# interstage_B2v2.net
KiCad netlist of a schematic drawn in EAGLE
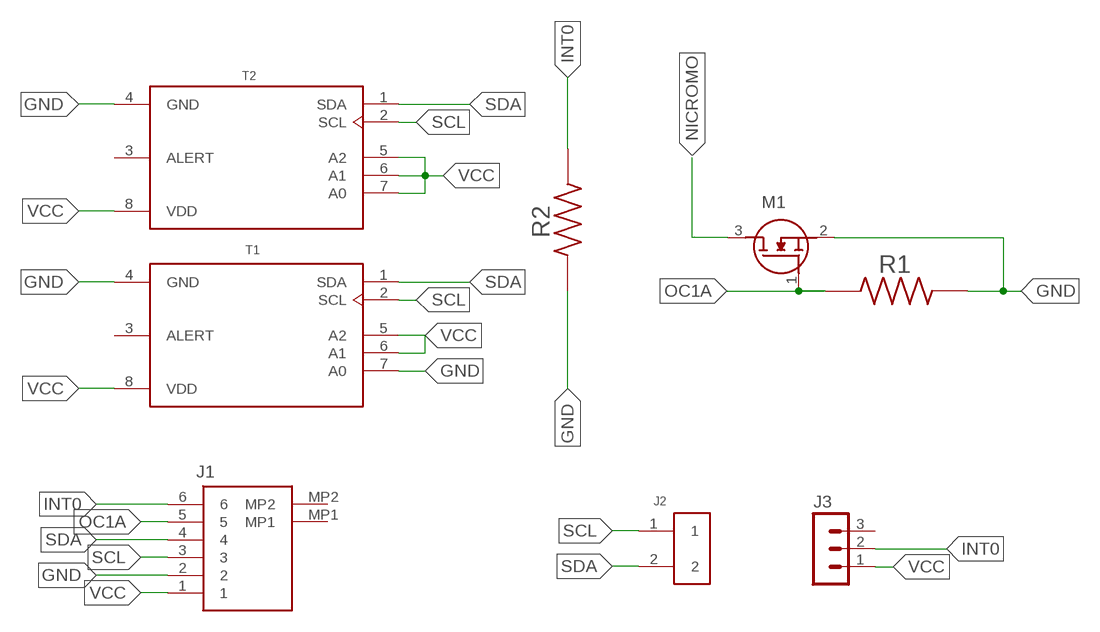
[diagram p0: schematic, sheet 1]

(export (version "E")
  (design (tool "Eeschema 10.0.6"))
  (components
    (comp (ref "J1")
      (value "53261-7006")
      (footprint "eagle-import:532617006")
      (fields (field (name "MOUSER_PART_NUMBER") "538-53261-7006"))
      (libsource (lib "eagle-import") (part "53261-7006"))
    )
    (comp (ref "J2")
      (value "0532610271")
      (footprint "eagle-import:MOLEX_0532610271")
      (fields (field (name "MF") "Molex"))
      (libsource (lib "eagle-import") (part "0532610271"))
    )
    (comp (ref "J3")
      (value "MA03-1")
      (footprint "eagle-import:MA03-1")
      (libsource (lib "eagle-import") (part "MA03-1"))
    )
    (comp (ref "M1")
      (value "PMV16XNR")
      (footprint "eagle-import:SOT95P230X110-3N")
      (fields (field (name "MOUSER_PART_NUMBER") "771-PMV16XNR"))
      (libsource (lib "eagle-import") (part "PMV16XNR"))
    )
    (comp (ref "R1")
      (value "330")
      (footprint "eagle-import:RESC3216X70N")
      (fields
        (field (name "DIGI-KEY_PART_NUMBER") "P330BCCT-ND")
        (field (name "MF") "Panasonic Electronic")
        (field (name "MP") "ERA-8AEB331V")
      )
      (libsource (lib "eagle-import") (part "ERA-8AEB331V"))
    )
    (comp (ref "R2")
      (value "330")
      (footprint "eagle-import:RESC3216X70N")
      (fields
        (field (name "DIGI-KEY_PART_NUMBER") "P330BCCT-ND")
        (field (name "MF") "Panasonic Electronic")
        (field (name "MP") "ERA-8AEB331V")
      )
      (libsource (lib "eagle-import") (part "ERA-8AEB331V"))
    )
    (comp (ref "T1")
      (value "MCP9808T-E/MS")
      (footprint "eagle-import:SOP65P490X110-8N")
      (fields (field (name "DIGI-KEY_PART_NUMBER") "MCP9808T-E/MSCT-ND") (field (name "MF") "Microchip"))
      (libsource (lib "eagle-import") (part "MCP9808T-E/MS"))
    )
    (comp (ref "T2")
      (value "MCP9808T-E/MS")
      (footprint "eagle-import:SOP65P490X110-8N")
      (fields (field (name "DIGI-KEY_PART_NUMBER") "MCP9808T-E/MSCT-ND") (field (name "MF") "Microchip"))
      (libsource (lib "eagle-import") (part "MCP9808T-E/MS"))
    )
  )
  (nets
    (net (code "1") (name "GND") (class "Default")
      (node (ref "J1") (pin "2") (pinfunction "2_2") (pintype "bidirectional"))
      (node (ref "M1") (pin "2") (pinfunction "S_2") (pintype "bidirectional"))
      (node (ref "R1") (pin "2") (pinfunction "2_2") (pintype "passive"))
      (node (ref "R2") (pin "1") (pinfunction "1_1") (pintype "passive"))
      (node (ref "T1") (pin "4") (pinfunction "GND_4") (pintype "power_in"))
      (node (ref "T1") (pin "7") (pinfunction "A0_7") (pintype "input"))
      (node (ref "T2") (pin "4") (pinfunction "GND_4") (pintype "power_in"))
    )
    (net (code "2") (name "INT0") (class "Default")
      (node (ref "J1") (pin "6") (pinfunction "6_6") (pintype "bidirectional"))
      (node (ref "J3") (pin "2") (pinfunction "2_2") (pintype "passive"))
      (node (ref "R2") (pin "2") (pinfunction "2_2") (pintype "passive"))
    )
    (net (code "3") (name "NICROMO") (class "Default")
      (node (ref "M1") (pin "3") (pinfunction "D_3") (pintype "bidirectional"))
    )
    (net (code "4") (name "OC1A") (class "Default")
      (node (ref "J1") (pin "5") (pinfunction "5_5") (pintype "bidirectional"))
      (node (ref "M1") (pin "1") (pinfunction "G_1") (pintype "bidirectional"))
      (node (ref "R1") (pin "1") (pinfunction "1_1") (pintype "passive"))
    )
    (net (code "5") (name "SCL") (class "Default")
      (node (ref "J1") (pin "3") (pinfunction "3_3") (pintype "bidirectional"))
      (node (ref "J2") (pin "1") (pinfunction "1_1") (pintype "passive"))
      (node (ref "T1") (pin "2") (pinfunction "SCL_2") (pintype "input"))
      (node (ref "T2") (pin "2") (pinfunction "SCL_2") (pintype "input"))
    )
    (net (code "6") (name "SDA") (class "Default")
      (node (ref "J1") (pin "4") (pinfunction "4_4") (pintype "bidirectional"))
      (node (ref "J2") (pin "2") (pinfunction "2_2") (pintype "passive"))
      (node (ref "T1") (pin "1") (pinfunction "SDA_1") (pintype "bidirectional"))
      (node (ref "T2") (pin "1") (pinfunction "SDA_1") (pintype "bidirectional"))
    )
    (net (code "7") (name "VCC") (class "Default")
      (node (ref "J1") (pin "1") (pinfunction "1_1") (pintype "bidirectional"))
      (node (ref "J3") (pin "1") (pinfunction "1_1") (pintype "passive"))
      (node (ref "T1") (pin "5") (pinfunction "A2_5") (pintype "input"))
      (node (ref "T1") (pin "6") (pinfunction "A1_6") (pintype "input"))
      (node (ref "T1") (pin "8") (pinfunction "VDD_8") (pintype "power_in"))
      (node (ref "T2") (pin "5") (pinfunction "A2_5") (pintype "input"))
      (node (ref "T2") (pin "6") (pinfunction "A1_6") (pintype "input"))
      (node (ref "T2") (pin "7") (pinfunction "A0_7") (pintype "input"))
      (node (ref "T2") (pin "8") (pinfunction "VDD_8") (pintype "power_in"))
    )
    (net (code "8") (name "unconnected-(J1-PadMP1)") (class "Default")
      (node (ref "J1") (pin "MP1") (pinfunction "MP1_MP1") (pintype "bidirectional"))
    )
    (net (code "9") (name "unconnected-(J1-PadMP2)") (class "Default")
      (node (ref "J1") (pin "MP2") (pinfunction "MP2_MP2") (pintype "bidirectional"))
    )
    (net (code "10") (name "unconnected-(J3-Pad3)") (class "Default")
      (node (ref "J3") (pin "3") (pinfunction "3_3") (pintype "passive"))
    )
    (net (code "11") (name "unconnected-(T1-ALERT-Pad3)") (class "Default")
      (node (ref "T1") (pin "3") (pinfunction "ALERT_3") (pintype "output"))
    )
    (net (code "12") (name "unconnected-(T2-ALERT-Pad3)") (class "Default")
      (node (ref "T2") (pin "3") (pinfunction "ALERT_3") (pintype "output"))
    )
  )
)
